# SOUND_BUZZER.net
KiCad netlist of a schematic drawn in Altium Designer
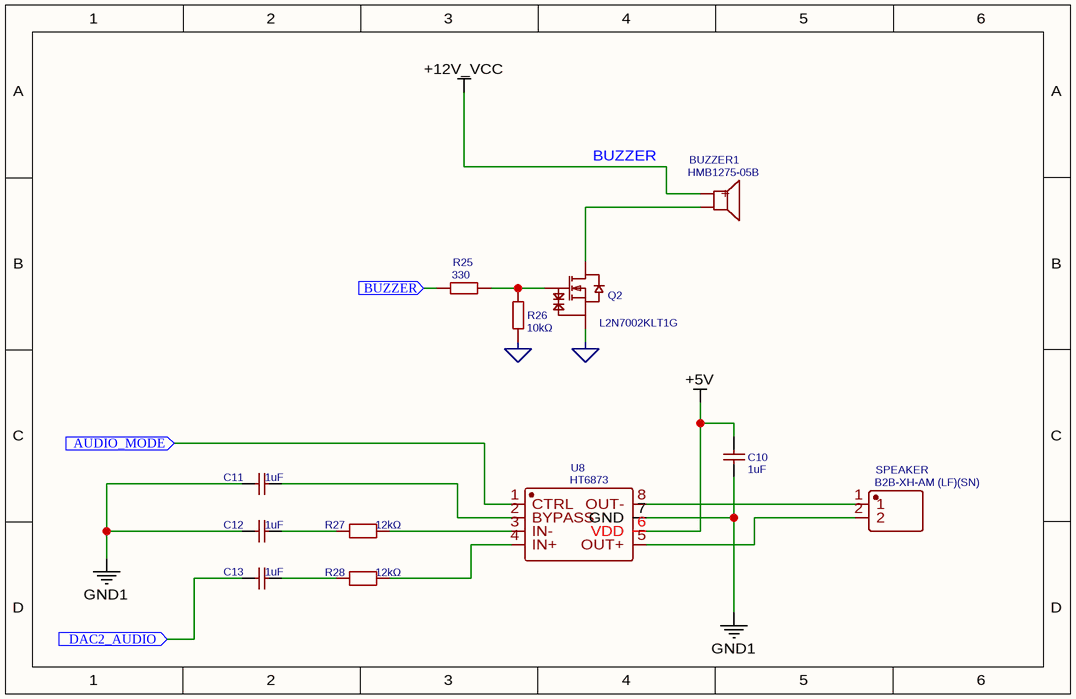
[diagram p0: SOUND BUZZER.schdoc]

(export (version "E")
  (design (tool "Eeschema 10.0.6"))
  (components
    (comp (ref "BUZZER1")
      (value "HMB1275-05B")
      (fields (field (name "BOM_SUPPLIER PART") "C96491"))
      (libsource (lib "altium-import") (part "root_0_HMB1275-05B_"))
    )
    (comp (ref "C10")
      (value "1uF")
      (fields
        (field (name "BOM_MANUFACTURER PART") "CC1206KKX7R8BB105")
        (field (name "BOM_SUPPLIER PART") "C107184")
      )
      (libsource (lib "altium-import") (part "root_3_1uF_"))
    )
    (comp (ref "C11")
      (value "1uF")
      (fields
        (field (name "BOM_MANUFACTURER PART") "CC1206KKX7R8BB105")
        (field (name "BOM_SUPPLIER PART") "C107184")
      )
      (libsource (lib "altium-import") (part "root_2_1uF_"))
    )
    (comp (ref "C12")
      (value "1uF")
      (fields
        (field (name "BOM_MANUFACTURER PART") "CC1206KKX7R8BB105")
        (field (name "BOM_SUPPLIER PART") "C107184")
      )
      (libsource (lib "altium-import") (part "root_2_1uF_"))
    )
    (comp (ref "C13")
      (value "1uF")
      (fields
        (field (name "BOM_MANUFACTURER PART") "CC1206KKX7R8BB105")
        (field (name "BOM_SUPPLIER PART") "C107184")
      )
      (libsource (lib "altium-import") (part "root_2_1uF_"))
    )
    (comp (ref "Q2")
      (value "L2N7002KLT1G")
      (fields
        (field (name "BOM_MANUFACTURER PART") "L2N7002SLT1G")
        (field (name "BOM_SUPPLIER PART") "C250818")
      )
      (libsource (lib "altium-import") (part "root_0_L2N7002KLT1G_"))
    )
    (comp (ref "R25")
      (value "330")
      (fields
        (field (name "BOM_MANUFACTURER PART") "AC0805FR-07330RL")
        (field (name "BOM_SUPPLIER PART") "C144564")
        (field (name "CONTRIBUTOR") "LCSC")
      )
      (libsource (lib "altium-import") (part "root_2_330_"))
    )
    (comp (ref "R26")
      (value "10kΩ")
      (fields
        (field (name "BOM_SUPPLIER PART") "C332266")
        (field (name "BOM_MANUFACTURER PART") "TR0805D10KP0550")
        (field (name "CONTRIBUTOR") "LCSC")
      )
      (libsource (lib "altium-import") (part "root_1_10kΩ_"))
    )
    (comp (ref "R27")
      (value "12kΩ")
      (fields
        (field (name "BOM_SUPPLIER PART") "C414966")
        (field (name "BOM_MANUFACTURER PART") "HP05W3J0123T5E")
        (field (name "CONTRIBUTOR") "LCSC")
      )
      (libsource (lib "altium-import") (part "root_0_12kΩ_"))
    )
    (comp (ref "R28")
      (value "12kΩ")
      (fields
        (field (name "BOM_SUPPLIER PART") "C414966")
        (field (name "BOM_MANUFACTURER PART") "HP05W3J0123T5E")
        (field (name "CONTRIBUTOR") "LCSC")
      )
      (libsource (lib "altium-import") (part "root_0_12kΩ_"))
    )
    (comp (ref "SPEAKER")
      (value "B2B-XH-AM (LF)(SN)")
      (fields (field (name "BOM_SUPPLIER PART") "C161869") (field (name "CONTRIBUTOR") "LCSC"))
      (libsource (lib "altium-import") (part "root_0_B2B-XH-AM (LF)(SN)_"))
    )
    (comp (ref "U8")
      (value "HT6873")
      (fields (field (name "BOM_SUPPLIER PART") "C94920"))
      (libsource (lib "altium-import") (part "root_0_HT6873_"))
    )
  )
  (nets
    (net (code "1") (name "+5V") (class "Default")
      (node (ref "C10") (pin "1") (pinfunction "1_1") (pintype "passive"))
      (node (ref "U8") (pin "6") (pinfunction "VDD_6") (pintype "passive"))
    )
    (net (code "2") (name "+12V_VCC") (class "Default")
      (node (ref "BUZZER1") (pin "1") (pinfunction "+_1") (pintype "passive"))
    )
    (net (code "3") (name "/AUDIO_MODE") (class "Default")
      (node (ref "U8") (pin "1") (pinfunction "CTRL_1") (pintype "passive"))
    )
    (net (code "4") (name "/BUZZER") (class "Default")
      (node (ref "R25") (pin "2") (pinfunction "2_2") (pintype "passive"))
    )
    (net (code "5") (name "/DAC2_AUDIO") (class "Default")
      (node (ref "C13") (pin "2") (pinfunction "2_2") (pintype "passive"))
    )
    (net (code "6") (name "GND1") (class "Default")
      (node (ref "C10") (pin "2") (pinfunction "2_2") (pintype "passive"))
      (node (ref "C11") (pin "2") (pinfunction "2_2") (pintype "passive"))
      (node (ref "C12") (pin "2") (pinfunction "2_2") (pintype "passive"))
      (node (ref "Q2") (pin "2") (pinfunction "S_2") (pintype "passive"))
      (node (ref "R26") (pin "1") (pinfunction "1_1") (pintype "passive"))
      (node (ref "U8") (pin "7") (pinfunction "GND_7") (pintype "passive"))
    )
    (net (code "7") (name "Net-(C12-Pad1)") (class "Default")
      (node (ref "C12") (pin "1") (pinfunction "1_1") (pintype "passive"))
      (node (ref "R27") (pin "1") (pinfunction "1_1") (pintype "passive"))
    )
    (net (code "8") (name "Net-(C13-Pad1)") (class "Default")
      (node (ref "C13") (pin "1") (pinfunction "1_1") (pintype "passive"))
      (node (ref "R28") (pin "1") (pinfunction "1_1") (pintype "passive"))
    )
    (net (code "9") (name "Net-(Q2-D)") (class "Default")
      (node (ref "BUZZER1") (pin "2") (pinfunction "2_2") (pintype "passive"))
      (node (ref "Q2") (pin "3") (pinfunction "D_3") (pintype "passive"))
    )
    (net (code "10") (name "Net-(Q2-G)") (class "Default")
      (node (ref "Q2") (pin "1") (pinfunction "G_1") (pintype "passive"))
      (node (ref "R25") (pin "1") (pinfunction "1_1") (pintype "passive"))
      (node (ref "R26") (pin "2") (pinfunction "2_2") (pintype "passive"))
    )
    (net (code "11") (name "Net-(U8-BYPASS)") (class "Default")
      (node (ref "C11") (pin "1") (pinfunction "1_1") (pintype "passive"))
      (node (ref "U8") (pin "2") (pinfunction "BYPASS_2") (pintype "passive"))
    )
    (net (code "12") (name "Net-(U8-IN+)") (class "Default")
      (node (ref "R28") (pin "2") (pinfunction "2_2") (pintype "passive"))
      (node (ref "U8") (pin "4") (pinfunction "IN+_4") (pintype "passive"))
    )
    (net (code "13") (name "Net-(U8-IN-)") (class "Default")
      (node (ref "R27") (pin "2") (pinfunction "2_2") (pintype "passive"))
      (node (ref "U8") (pin "3") (pinfunction "IN-_3") (pintype "passive"))
    )
    (net (code "14") (name "Net-(U8-OUT+)") (class "Default")
      (node (ref "SPEAKER") (pin "2") (pinfunction "2_2") (pintype "passive"))
      (node (ref "U8") (pin "5") (pinfunction "OUT+_5") (pintype "passive"))
    )
    (net (code "15") (name "Net-(U8-OUT-)") (class "Default")
      (node (ref "SPEAKER") (pin "1") (pinfunction "1_1") (pintype "passive"))
      (node (ref "U8") (pin "8") (pinfunction "OUT-_8") (pintype "passive"))
    )
  )
)
